# 8x8x8_LEDCUBE_Electronics.net
KiCad netlist of a schematic drawn in EAGLE
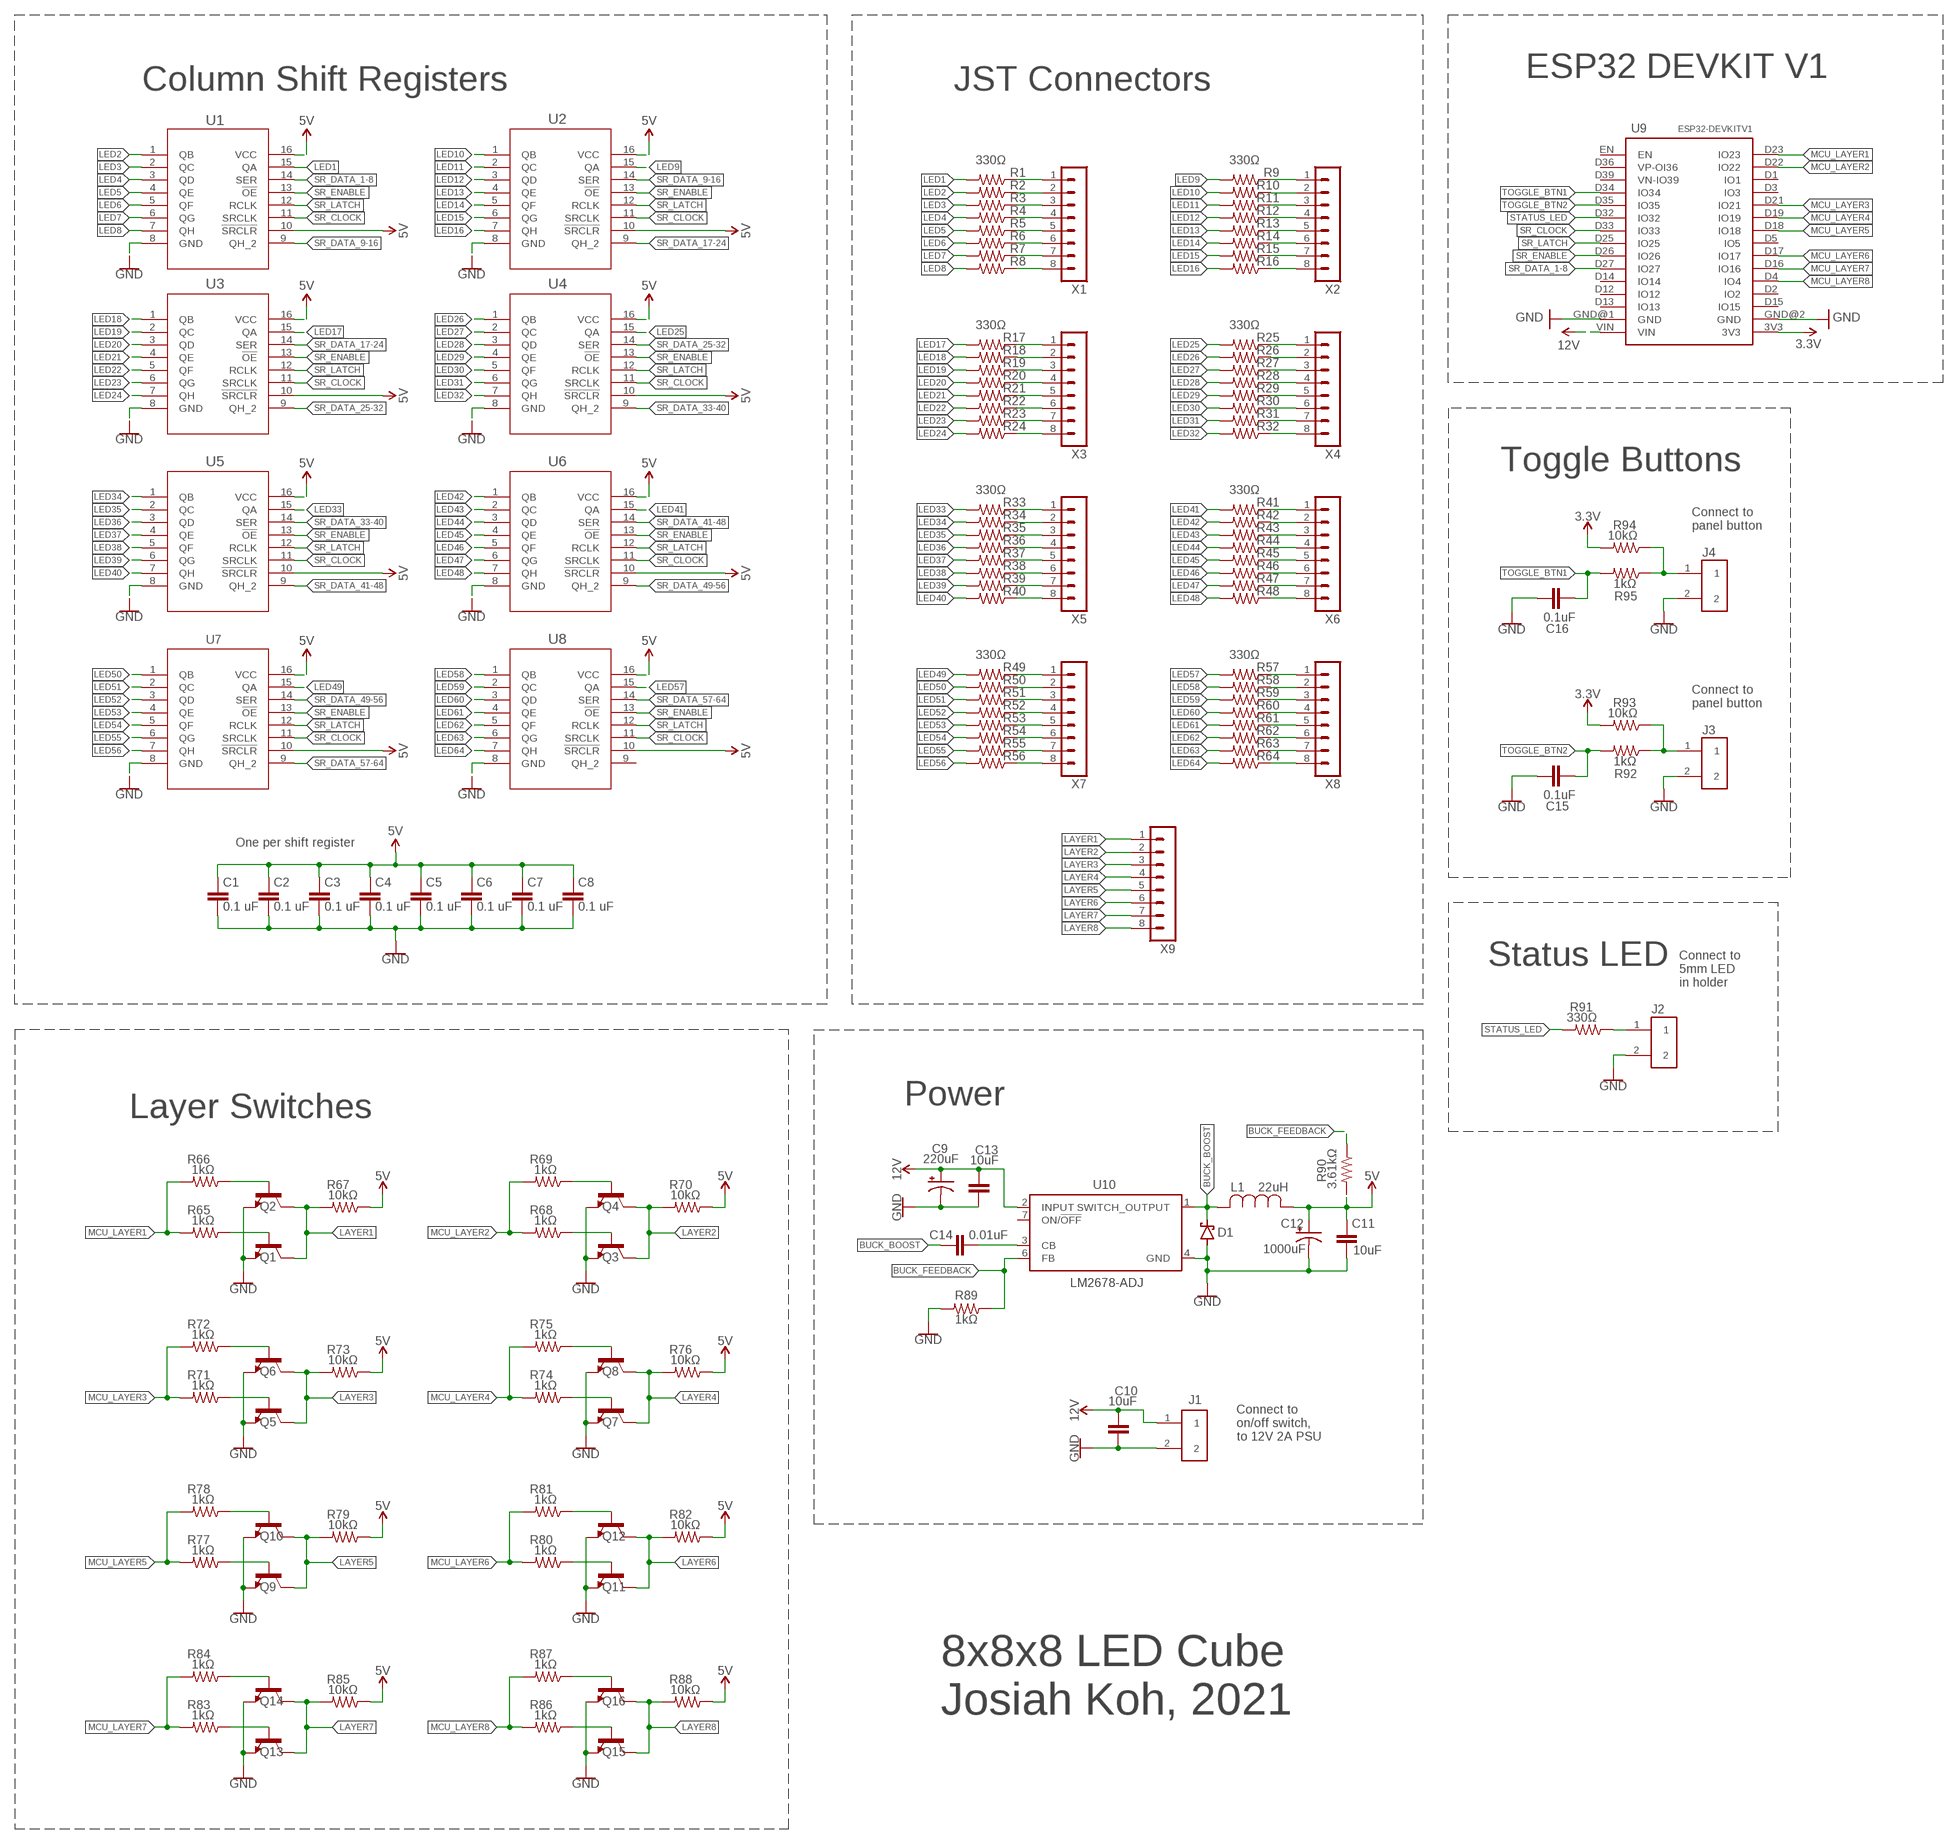
[diagram p0: schematic, sheet 1]

(export (version "E")
  (design (tool "Eeschema 10.0.6"))
  (components
    (comp (ref "C1")
      (value "0.1 uF")
      (footprint "eagle-import:C0805")
      (libsource (lib "eagle-import") (part "C-EUC0805"))
    )
    (comp (ref "C2")
      (value "0.1 uF")
      (footprint "eagle-import:C0805")
      (libsource (lib "eagle-import") (part "C-EUC0805"))
    )
    (comp (ref "C3")
      (value "0.1 uF")
      (footprint "eagle-import:C0805")
      (libsource (lib "eagle-import") (part "C-EUC0805"))
    )
    (comp (ref "C4")
      (value "0.1 uF")
      (footprint "eagle-import:C0805")
      (libsource (lib "eagle-import") (part "C-EUC0805"))
    )
    (comp (ref "C5")
      (value "0.1 uF")
      (footprint "eagle-import:C0805")
      (libsource (lib "eagle-import") (part "C-EUC0805"))
    )
    (comp (ref "C6")
      (value "0.1 uF")
      (footprint "eagle-import:C0805")
      (libsource (lib "eagle-import") (part "C-EUC0805"))
    )
    (comp (ref "C7")
      (value "0.1 uF")
      (footprint "eagle-import:C0805")
      (libsource (lib "eagle-import") (part "C-EUC0805"))
    )
    (comp (ref "C8")
      (value "0.1 uF")
      (footprint "eagle-import:C0805")
      (libsource (lib "eagle-import") (part "C-EUC0805"))
    )
    (comp (ref "C9")
      (value "220uF")
      (footprint "eagle-import:E3,5-10")
      (libsource (lib "eagle-import") (part "CPOL-USE3.5-10"))
    )
    (comp (ref "C10")
      (value "10uF")
      (footprint "eagle-import:C0805")
      (libsource (lib "eagle-import") (part "C-EUC0805"))
    )
    (comp (ref "C11")
      (value "10uF")
      (footprint "eagle-import:C0805")
      (libsource (lib "eagle-import") (part "C-EUC0805"))
    )
    (comp (ref "C12")
      (value "1000uF")
      (footprint "eagle-import:E3,5-10")
      (libsource (lib "eagle-import") (part "CPOL-USE3.5-10"))
    )
    (comp (ref "C13")
      (value "10uF")
      (footprint "eagle-import:C0805")
      (libsource (lib "eagle-import") (part "C-EUC0805"))
    )
    (comp (ref "C14")
      (value "0.01uF")
      (footprint "eagle-import:C0805")
      (libsource (lib "eagle-import") (part "C-EUC0805"))
    )
    (comp (ref "C15")
      (value "0.1uF")
      (footprint "eagle-import:C0805")
      (libsource (lib "eagle-import") (part "C-EUC0805"))
    )
    (comp (ref "C16")
      (value "0.1uF")
      (footprint "eagle-import:C0805")
      (libsource (lib "eagle-import") (part "C-EUC0805"))
    )
    (comp (ref "D1")
      (value "STPS5L60S")
      (footprint "eagle-import:SMC")
      (libsource (lib "eagle-import") (part "SCHOTTKY-DIODESMC"))
    )
    (comp (ref "J1")
      (value "1935161")
      (footprint "eagle-import:PHOENIX_1935161")
      (fields (field (name "DIGI-KEY_PART_NUMBER") "277-1667-ND") (field (name "MF") "Phoenix Contact"))
      (libsource (lib "eagle-import") (part "1935161"))
    )
    (comp (ref "J2")
      (value "1935161")
      (footprint "eagle-import:PHOENIX_1935161")
      (fields (field (name "DIGI-KEY_PART_NUMBER") "277-1667-ND") (field (name "MF") "Phoenix Contact"))
      (libsource (lib "eagle-import") (part "1935161"))
    )
    (comp (ref "J3")
      (value "1935161")
      (footprint "eagle-import:PHOENIX_1935161")
      (fields (field (name "DIGI-KEY_PART_NUMBER") "277-1667-ND") (field (name "MF") "Phoenix Contact"))
      (libsource (lib "eagle-import") (part "1935161"))
    )
    (comp (ref "J4")
      (value "1935161")
      (footprint "eagle-import:PHOENIX_1935161")
      (fields (field (name "DIGI-KEY_PART_NUMBER") "277-1667-ND") (field (name "MF") "Phoenix Contact"))
      (libsource (lib "eagle-import") (part "1935161"))
    )
    (comp (ref "L1")
      (value "22uH")
      (footprint "eagle-import:AIAP-03_ABR")
      (fields (field (name "MANUFACTURER_PART_NUMBER") "AIAP-03-220K"))
      (libsource (lib "eagle-import") (part "AIAP-03-220K"))
    )
    (comp (ref "Q1")
      (value "600mA/40V")
      (footprint "eagle-import:TO-92")
      (libsource (lib "eagle-import") (part "TRANS_NPN-P2N2222A"))
    )
    (comp (ref "Q2")
      (value "600mA/40V")
      (footprint "eagle-import:TO-92")
      (libsource (lib "eagle-import") (part "TRANS_NPN-P2N2222A"))
    )
    (comp (ref "Q3")
      (value "600mA/40V")
      (footprint "eagle-import:TO-92")
      (libsource (lib "eagle-import") (part "TRANS_NPN-P2N2222A"))
    )
    (comp (ref "Q4")
      (value "600mA/40V")
      (footprint "eagle-import:TO-92")
      (libsource (lib "eagle-import") (part "TRANS_NPN-P2N2222A"))
    )
    (comp (ref "Q5")
      (value "600mA/40V")
      (footprint "eagle-import:TO-92")
      (libsource (lib "eagle-import") (part "TRANS_NPN-P2N2222A"))
    )
    (comp (ref "Q6")
      (value "600mA/40V")
      (footprint "eagle-import:TO-92")
      (libsource (lib "eagle-import") (part "TRANS_NPN-P2N2222A"))
    )
    (comp (ref "Q7")
      (value "600mA/40V")
      (footprint "eagle-import:TO-92")
      (libsource (lib "eagle-import") (part "TRANS_NPN-P2N2222A"))
    )
    (comp (ref "Q8")
      (value "600mA/40V")
      (footprint "eagle-import:TO-92")
      (libsource (lib "eagle-import") (part "TRANS_NPN-P2N2222A"))
    )
    (comp (ref "Q9")
      (value "600mA/40V")
      (footprint "eagle-import:TO-92")
      (libsource (lib "eagle-import") (part "TRANS_NPN-P2N2222A"))
    )
    (comp (ref "Q10")
      (value "600mA/40V")
      (footprint "eagle-import:TO-92")
      (libsource (lib "eagle-import") (part "TRANS_NPN-P2N2222A"))
    )
    (comp (ref "Q11")
      (value "600mA/40V")
      (footprint "eagle-import:TO-92")
      (libsource (lib "eagle-import") (part "TRANS_NPN-P2N2222A"))
    )
    (comp (ref "Q12")
      (value "600mA/40V")
      (footprint "eagle-import:TO-92")
      (libsource (lib "eagle-import") (part "TRANS_NPN-P2N2222A"))
    )
    (comp (ref "Q13")
      (value "600mA/40V")
      (footprint "eagle-import:TO-92")
      (libsource (lib "eagle-import") (part "TRANS_NPN-P2N2222A"))
    )
    (comp (ref "Q14")
      (value "600mA/40V")
      (footprint "eagle-import:TO-92")
      (libsource (lib "eagle-import") (part "TRANS_NPN-P2N2222A"))
    )
    (comp (ref "Q15")
      (value "600mA/40V")
      (footprint "eagle-import:TO-92")
      (libsource (lib "eagle-import") (part "TRANS_NPN-P2N2222A"))
    )
    (comp (ref "Q16")
      (value "600mA/40V")
      (footprint "eagle-import:TO-92")
      (libsource (lib "eagle-import") (part "TRANS_NPN-P2N2222A"))
    )
    (comp (ref "R1")
      (value "330Ω")
      (footprint "eagle-import:R0805")
      (libsource (lib "eagle-import") (part "R-US_R0805"))
    )
    (comp (ref "R2")
      (value "330Ω")
      (footprint "eagle-import:R0805")
      (libsource (lib "eagle-import") (part "R-US_R0805"))
    )
    (comp (ref "R3")
      (value "330Ω")
      (footprint "eagle-import:R0805")
      (libsource (lib "eagle-import") (part "R-US_R0805"))
    )
    (comp (ref "R4")
      (value "330Ω")
      (footprint "eagle-import:R0805")
      (libsource (lib "eagle-import") (part "R-US_R0805"))
    )
    (comp (ref "R5")
      (value "330Ω")
      (footprint "eagle-import:R0805")
      (libsource (lib "eagle-import") (part "R-US_R0805"))
    )
    (comp (ref "R6")
      (value "330Ω")
      (footprint "eagle-import:R0805")
      (libsource (lib "eagle-import") (part "R-US_R0805"))
    )
    (comp (ref "R7")
      (value "330Ω")
      (footprint "eagle-import:R0805")
      (libsource (lib "eagle-import") (part "R-US_R0805"))
    )
    (comp (ref "R8")
      (value "330Ω")
      (footprint "eagle-import:R0805")
      (libsource (lib "eagle-import") (part "R-US_R0805"))
    )
    (comp (ref "R9")
      (value "330Ω")
      (footprint "eagle-import:R0805")
      (libsource (lib "eagle-import") (part "R-US_R0805"))
    )
    (comp (ref "R10")
      (value "330Ω")
      (footprint "eagle-import:R0805")
      (libsource (lib "eagle-import") (part "R-US_R0805"))
    )
    (comp (ref "R11")
      (value "330Ω")
      (footprint "eagle-import:R0805")
      (libsource (lib "eagle-import") (part "R-US_R0805"))
    )
    (comp (ref "R12")
      (value "330Ω")
      (footprint "eagle-import:R0805")
      (libsource (lib "eagle-import") (part "R-US_R0805"))
    )
    (comp (ref "R13")
      (value "330Ω")
      (footprint "eagle-import:R0805")
      (libsource (lib "eagle-import") (part "R-US_R0805"))
    )
    (comp (ref "R14")
      (value "330Ω")
      (footprint "eagle-import:R0805")
      (libsource (lib "eagle-import") (part "R-US_R0805"))
    )
    (comp (ref "R15")
      (value "330Ω")
      (footprint "eagle-import:R0805")
      (libsource (lib "eagle-import") (part "R-US_R0805"))
    )
    (comp (ref "R16")
      (value "330Ω")
      (footprint "eagle-import:R0805")
      (libsource (lib "eagle-import") (part "R-US_R0805"))
    )
    (comp (ref "R17")
      (value "330Ω")
      (footprint "eagle-import:R0805")
      (libsource (lib "eagle-import") (part "R-US_R0805"))
    )
    (comp (ref "R18")
      (value "330Ω")
      (footprint "eagle-import:R0805")
      (libsource (lib "eagle-import") (part "R-US_R0805"))
    )
    (comp (ref "R19")
      (value "330Ω")
      (footprint "eagle-import:R0805")
      (libsource (lib "eagle-import") (part "R-US_R0805"))
    )
    (comp (ref "R20")
      (value "330Ω")
      (footprint "eagle-import:R0805")
      (libsource (lib "eagle-import") (part "R-US_R0805"))
    )
    (comp (ref "R21")
      (value "330Ω")
      (footprint "eagle-import:R0805")
      (libsource (lib "eagle-import") (part "R-US_R0805"))
    )
    (comp (ref "R22")
      (value "330Ω")
      (footprint "eagle-import:R0805")
      (libsource (lib "eagle-import") (part "R-US_R0805"))
    )
    (comp (ref "R23")
      (value "330Ω")
      (footprint "eagle-import:R0805")
      (libsource (lib "eagle-import") (part "R-US_R0805"))
    )
    (comp (ref "R24")
      (value "330Ω")
      (footprint "eagle-import:R0805")
      (libsource (lib "eagle-import") (part "R-US_R0805"))
    )
    (comp (ref "R25")
      (value "330Ω")
      (footprint "eagle-import:R0805")
      (libsource (lib "eagle-import") (part "R-US_R0805"))
    )
    (comp (ref "R26")
      (value "330Ω")
      (footprint "eagle-import:R0805")
      (libsource (lib "eagle-import") (part "R-US_R0805"))
    )
    (comp (ref "R27")
      (value "330Ω")
      (footprint "eagle-import:R0805")
      (libsource (lib "eagle-import") (part "R-US_R0805"))
    )
    (comp (ref "R28")
      (value "330Ω")
      (footprint "eagle-import:R0805")
      (libsource (lib "eagle-import") (part "R-US_R0805"))
    )
    (comp (ref "R29")
      (value "330Ω")
      (footprint "eagle-import:R0805")
      (libsource (lib "eagle-import") (part "R-US_R0805"))
    )
    (comp (ref "R30")
      (value "330Ω")
      (footprint "eagle-import:R0805")
      (libsource (lib "eagle-import") (part "R-US_R0805"))
    )
    (comp (ref "R31")
      (value "330Ω")
      (footprint "eagle-import:R0805")
      (libsource (lib "eagle-import") (part "R-US_R0805"))
    )
    (comp (ref "R32")
      (value "330Ω")
      (footprint "eagle-import:R0805")
      (libsource (lib "eagle-import") (part "R-US_R0805"))
    )
    (comp (ref "R33")
      (value "330Ω")
      (footprint "eagle-import:R0805")
      (libsource (lib "eagle-import") (part "R-US_R0805"))
    )
    (comp (ref "R34")
      (value "330Ω")
      (footprint "eagle-import:R0805")
      (libsource (lib "eagle-import") (part "R-US_R0805"))
    )
    (comp (ref "R35")
      (value "330Ω")
      (footprint "eagle-import:R0805")
      (libsource (lib "eagle-import") (part "R-US_R0805"))
    )
    (comp (ref "R36")
      (value "330Ω")
      (footprint "eagle-import:R0805")
      (libsource (lib "eagle-import") (part "R-US_R0805"))
    )
    (comp (ref "R37")
      (value "330Ω")
      (footprint "eagle-import:R0805")
      (libsource (lib "eagle-import") (part "R-US_R0805"))
    )
    (comp (ref "R38")
      (value "330Ω")
      (footprint "eagle-import:R0805")
      (libsource (lib "eagle-import") (part "R-US_R0805"))
    )
    (comp (ref "R39")
      (value "330Ω")
      (footprint "eagle-import:R0805")
      (libsource (lib "eagle-import") (part "R-US_R0805"))
    )
    (comp (ref "R40")
      (value "330Ω")
      (footprint "eagle-import:R0805")
      (libsource (lib "eagle-import") (part "R-US_R0805"))
    )
    (comp (ref "R41")
      (value "330Ω")
      (footprint "eagle-import:R0805")
      (libsource (lib "eagle-import") (part "R-US_R0805"))
    )
    (comp (ref "R42")
      (value "330Ω")
      (footprint "eagle-import:R0805")
      (libsource (lib "eagle-import") (part "R-US_R0805"))
    )
    (comp (ref "R43")
      (value "330Ω")
      (footprint "eagle-import:R0805")
      (libsource (lib "eagle-import") (part "R-US_R0805"))
    )
    (comp (ref "R44")
      (value "330Ω")
      (footprint "eagle-import:R0805")
      (libsource (lib "eagle-import") (part "R-US_R0805"))
    )
    (comp (ref "R45")
      (value "330Ω")
      (footprint "eagle-import:R0805")
      (libsource (lib "eagle-import") (part "R-US_R0805"))
    )
    (comp (ref "R46")
      (value "330Ω")
      (footprint "eagle-import:R0805")
      (libsource (lib "eagle-import") (part "R-US_R0805"))
    )
    (comp (ref "R47")
      (value "330Ω")
      (footprint "eagle-import:R0805")
      (libsource (lib "eagle-import") (part "R-US_R0805"))
    )
    (comp (ref "R48")
      (value "330Ω")
      (footprint "eagle-import:R0805")
      (libsource (lib "eagle-import") (part "R-US_R0805"))
    )
    (comp (ref "R49")
      (value "330Ω")
      (footprint "eagle-import:R0805")
      (libsource (lib "eagle-import") (part "R-US_R0805"))
    )
    (comp (ref "R50")
      (value "330Ω")
      (footprint "eagle-import:R0805")
      (libsource (lib "eagle-import") (part "R-US_R0805"))
    )
    (comp (ref "R51")
      (value "330Ω")
      (footprint "eagle-import:R0805")
      (libsource (lib "eagle-import") (part "R-US_R0805"))
    )
    (comp (ref "R52")
      (value "330Ω")
      (footprint "eagle-import:R0805")
      (libsource (lib "eagle-import") (part "R-US_R0805"))
    )
    (comp (ref "R53")
      (value "330Ω")
      (footprint "eagle-import:R0805")
      (libsource (lib "eagle-import") (part "R-US_R0805"))
    )
    (comp (ref "R54")
      (value "330Ω")
      (footprint "eagle-import:R0805")
      (libsource (lib "eagle-import") (part "R-US_R0805"))
    )
    (comp (ref "R55")
      (value "330Ω")
      (footprint "eagle-import:R0805")
      (libsource (lib "eagle-import") (part "R-US_R0805"))
    )
    (comp (ref "R56")
      (value "330Ω")
      (footprint "eagle-import:R0805")
      (libsource (lib "eagle-import") (part "R-US_R0805"))
    )
    (comp (ref "R57")
      (value "330Ω")
      (footprint "eagle-import:R0805")
      (libsource (lib "eagle-import") (part "R-US_R0805"))
    )
    (comp (ref "R58")
      (value "330Ω")
      (footprint "eagle-import:R0805")
      (libsource (lib "eagle-import") (part "R-US_R0805"))
    )
    (comp (ref "R59")
      (value "330Ω")
      (footprint "eagle-import:R0805")
      (libsource (lib "eagle-import") (part "R-US_R0805"))
    )
    (comp (ref "R60")
      (value "330Ω")
      (footprint "eagle-import:R0805")
      (libsource (lib "eagle-import") (part "R-US_R0805"))
    )
    (comp (ref "R61")
      (value "330Ω")
      (footprint "eagle-import:R0805")
      (libsource (lib "eagle-import") (part "R-US_R0805"))
    )
    (comp (ref "R62")
      (value "330Ω")
      (footprint "eagle-import:R0805")
      (libsource (lib "eagle-import") (part "R-US_R0805"))
    )
    (comp (ref "R63")
      (value "330Ω")
      (footprint "eagle-import:R0805")
      (libsource (lib "eagle-import") (part "R-US_R0805"))
    )
    (comp (ref "R64")
      (value "330Ω")
      (footprint "eagle-import:R0805")
      (libsource (lib "eagle-import") (part "R-US_R0805"))
    )
    (comp (ref "R65")
      (value "1kΩ")
      (footprint "eagle-import:R0805")
      (libsource (lib "eagle-import") (part "R-US_R0805"))
    )
    (comp (ref "R66")
      (value "1kΩ")
      (footprint "eagle-import:R0805")
      (libsource (lib "eagle-import") (part "R-US_R0805"))
    )
    (comp (ref "R67")
      (value "10kΩ")
      (footprint "eagle-import:R0805")
      (libsource (lib "eagle-import") (part "R-US_R0805"))
    )
    (comp (ref "R68")
      (value "1kΩ")
      (footprint "eagle-import:R0805")
      (libsource (lib "eagle-import") (part "R-US_R0805"))
    )
    (comp (ref "R69")
      (value "1kΩ")
      (footprint "eagle-import:R0805")
      (libsource (lib "eagle-import") (part "R-US_R0805"))
    )
    (comp (ref "R70")
      (value "10kΩ")
      (footprint "eagle-import:R0805")
      (libsource (lib "eagle-import") (part "R-US_R0805"))
    )
    (comp (ref "R71")
      (value "1kΩ")
      (footprint "eagle-import:R0805")
      (libsource (lib "eagle-import") (part "R-US_R0805"))
    )
    (comp (ref "R72")
      (value "1kΩ")
      (footprint "eagle-import:R0805")
      (libsource (lib "eagle-import") (part "R-US_R0805"))
    )
    (comp (ref "R73")
      (value "10kΩ")
      (footprint "eagle-import:R0805")
      (libsource (lib "eagle-import") (part "R-US_R0805"))
    )
    (comp (ref "R74")
      (value "1kΩ")
      (footprint "eagle-import:R0805")
      (libsource (lib "eagle-import") (part "R-US_R0805"))
    )
    (comp (ref "R75")
      (value "1kΩ")
      (footprint "eagle-import:R0805")
      (libsource (lib "eagle-import") (part "R-US_R0805"))
    )
    (comp (ref "R76")
      (value "10kΩ")
      (footprint "eagle-import:R0805")
      (libsource (lib "eagle-import") (part "R-US_R0805"))
    )
    (comp (ref "R77")
      (value "1kΩ")
      (footprint "eagle-import:R0805")
      (libsource (lib "eagle-import") (part "R-US_R0805"))
    )
    (comp (ref "R78")
      (value "1kΩ")
      (footprint "eagle-import:R0805")
      (libsource (lib "eagle-import") (part "R-US_R0805"))
    )
    (comp (ref "R79")
      (value "10kΩ")
      (footprint "eagle-import:R0805")
      (libsource (lib "eagle-import") (part "R-US_R0805"))
    )
    (comp (ref "R80")
      (value "1kΩ")
      (footprint "eagle-import:R0805")
      (libsource (lib "eagle-import") (part "R-US_R0805"))
    )
    (comp (ref "R81")
      (value "1kΩ")
      (footprint "eagle-import:R0805")
      (libsource (lib "eagle-import") (part "R-US_R0805"))
    )
    (comp (ref "R82")
      (value "10kΩ")
      (footprint "eagle-import:R0805")
      (libsource (lib "eagle-import") (part "R-US_R0805"))
    )
    (comp (ref "R83")
      (value "1kΩ")
      (footprint "eagle-import:R0805")
      (libsource (lib "eagle-import") (part "R-US_R0805"))
    )
    (comp (ref "R84")
      (value "1kΩ")
      (footprint "eagle-import:R0805")
      (libsource (lib "eagle-import") (part "R-US_R0805"))
    )
    (comp (ref "R85")
      (value "10kΩ")
      (footprint "eagle-import:R0805")
      (libsource (lib "eagle-import") (part "R-US_R0805"))
    )
    (comp (ref "R86")
      (value "1kΩ")
      (footprint "eagle-import:R0805")
      (libsource (lib "eagle-import") (part "R-US_R0805"))
    )
    (comp (ref "R87")
      (value "1kΩ")
      (footprint "eagle-import:R0805")
      (libsource (lib "eagle-import") (part "R-US_R0805"))
    )
    (comp (ref "R88")
      (value "10kΩ")
      (footprint "eagle-import:R0805")
      (libsource (lib "eagle-import") (part "R-US_R0805"))
    )
    (comp (ref "R89")
      (value "1kΩ")
      (footprint "eagle-import:R0805")
      (libsource (lib "eagle-import") (part "R-US_R0805"))
    )
    (comp (ref "R90")
      (value "3.61kΩ")
      (footprint "eagle-import:R0805")
      (libsource (lib "eagle-import") (part "R-US_R0805"))
    )
    (comp (ref "R91")
      (value "330Ω")
      (footprint "eagle-import:R0805")
      (libsource (lib "eagle-import") (part "R-US_R0805"))
    )
    (comp (ref "R92")
      (value "1kΩ")
      (footprint "eagle-import:R0805")
      (libsource (lib "eagle-import") (part "R-US_R0805"))
    )
    (comp (ref "R93")
      (value "10kΩ")
      (footprint "eagle-import:R0805")
      (libsource (lib "eagle-import") (part "R-US_R0805"))
    )
    (comp (ref "R94")
      (value "10kΩ")
      (footprint "eagle-import:R0805")
      (libsource (lib "eagle-import") (part "R-US_R0805"))
    )
    (comp (ref "R95")
      (value "1kΩ")
      (footprint "eagle-import:R0805")
      (libsource (lib "eagle-import") (part "R-US_R0805"))
    )
    (comp (ref "U1")
      (value "SN74HC595N")
      (footprint "eagle-import:N16")
      (fields
        (field (name "GENERIC_PART_NUMBER") "SN74HC595")
        (field (name "MANUFACTURER") "Texas Instruments")
      )
      (libsource (lib "eagle-import") (part "SN74HC595N"))
    )
    (comp (ref "U2")
      (value "SN74HC595N")
      (footprint "eagle-import:N16")
      (fields
        (field (name "GENERIC_PART_NUMBER") "SN74HC595")
        (field (name "MANUFACTURER") "Texas Instruments")
      )
      (libsource (lib "eagle-import") (part "SN74HC595N"))
    )
    (comp (ref "U3")
      (value "SN74HC595N")
      (footprint "eagle-import:N16")
      (fields
        (field (name "GENERIC_PART_NUMBER") "SN74HC595")
        (field (name "MANUFACTURER") "Texas Instruments")
      )
      (libsource (lib "eagle-import") (part "SN74HC595N"))
    )
    (comp (ref "U4")
      (value "SN74HC595N")
      (footprint "eagle-import:N16")
      (fields
        (field (name "GENERIC_PART_NUMBER") "SN74HC595")
        (field (name "MANUFACTURER") "Texas Instruments")
      )
      (libsource (lib "eagle-import") (part "SN74HC595N"))
    )
    (comp (ref "U5")
      (value "SN74HC595N")
      (footprint "eagle-import:N16")
      (fields
        (field (name "GENERIC_PART_NUMBER") "SN74HC595")
        (field (name "MANUFACTURER") "Texas Instruments")
      )
      (libsource (lib "eagle-import") (part "SN74HC595N"))
    )
    (comp (ref "U6")
      (value "SN74HC595N")
      (footprint "eagle-import:N16")
      (fields
        (field (name "GENERIC_PART_NUMBER") "SN74HC595")
        (field (name "MANUFACTURER") "Texas Instruments")
      )
      (libsource (lib "eagle-import") (part "SN74HC595N"))
    )
    (comp (ref "U7")
      (value "SN74HC595N")
      (footprint "eagle-import:N16")
      (fields
        (field (name "GENERIC_PART_NUMBER") "SN74HC595")
        (field (name "MANUFACTURER") "Texas Instruments")
      )
      (libsource (lib "eagle-import") (part "SN74HC595N"))
    )
    (comp (ref "U8")
      (value "SN74HC595N")
      (footprint "eagle-import:N16")
      (fields
        (field (name "GENERIC_PART_NUMBER") "SN74HC595")
        (field (name "MANUFACTURER") "Texas Instruments")
      )
      (libsource (lib "eagle-import") (part "SN74HC595N"))
    )
    (comp (ref "U9")
      (value "ESP32DEVKITV1")
      (footprint "eagle-import:ESP32-DEVKITV1")
      (libsource (lib "eagle-import") (part "ESP32DEVKITV1"))
    )
    (comp (ref "U10")
      (value "LM2678-ADJ")
      (footprint "eagle-import:TO127P1041X469X2199-7N")
      (fields
        (field (name "DIGI-KEY_PART_NUMBER") "LM2678T-ADJ/NOPB-ND")
        (field (name "MF") "Texas Instruments")
        (field (name "MP") "LM2678T-ADJ/NOPB")
        (field (name "SPICEPREFIX") "X")
      )
      (libsource (lib "eagle-import") (part "LM2678T-ADJ/NOPB"))
    )
    (comp (ref "X1")
      (value "B8B-PH-KL")
      (footprint "eagle-import:B8B-PH-K-S")
      (libsource (lib "eagle-import") (part "B8B-PH-KL"))
    )
    (comp (ref "X2")
      (value "B8B-PH-KL")
      (footprint "eagle-import:B8B-PH-K-S")
      (libsource (lib "eagle-import") (part "B8B-PH-KL"))
    )
    (comp (ref "X3")
      (value "B8B-PH-KL")
      (footprint "eagle-import:B8B-PH-K-S")
      (libsource (lib "eagle-import") (part "B8B-PH-KL"))
    )
    (comp (ref "X4")
      (value "B8B-PH-KL")
      (footprint "eagle-import:B8B-PH-K-S")
      (libsource (lib "eagle-import") (part "B8B-PH-KL"))
    )
    (comp (ref "X5")
      (value "B8B-PH-KL")
      (footprint "eagle-import:B8B-PH-K-S")
      (libsource (lib "eagle-import") (part "B8B-PH-KL"))
    )
    (comp (ref "X6")
      (value "B8B-PH-KL")
      (footprint "eagle-import:B8B-PH-K-S")
      (libsource (lib "eagle-import") (part "B8B-PH-KL"))
    )
    (comp (ref "X7")
      (value "B8B-PH-KL")
      (footprint "eagle-import:B8B-PH-K-S")
      (libsource (lib "eagle-import") (part "B8B-PH-KL"))
    )
    (comp (ref "X8")
      (value "B8B-PH-KL")
      (footprint "eagle-import:B8B-PH-K-S")
      (libsource (lib "eagle-import") (part "B8B-PH-KL"))
    )
    (comp (ref "X9")
      (value "B8B-PH-KL")
      (footprint "eagle-import:B8B-PH-K-S")
      (libsource (lib "eagle-import") (part "B8B-PH-KL"))
    )
  )
  (nets
    (net (code "1") (name "3.3V") (class "Default")
      (node (ref "R93") (pin "2") (pinfunction "2_2") (pintype "passive"))
      (node (ref "R94") (pin "2") (pinfunction "2_2") (pintype "passive"))
      (node (ref "U9") (pin "3V3") (pinfunction "3V3_3V3") (pintype "bidirectional"))
    )
    (net (code "2") (name "5V") (class "Default")
      (node (ref "C1") (pin "1") (pinfunction "1_1") (pintype "passive"))
      (node (ref "C11") (pin "1") (pinfunction "1_1") (pintype "passive"))
      (node (ref "C12") (pin "+") (pinfunction "+_+") (pintype "passive"))
      (node (ref "C2") (pin "1") (pinfunction "1_1") (pintype "passive"))
      (node (ref "C3") (pin "1") (pinfunction "1_1") (pintype "passive"))
      (node (ref "C4") (pin "1") (pinfunction "1_1") (pintype "passive"))
      (node (ref "C5") (pin "1") (pinfunction "1_1") (pintype "passive"))
      (node (ref "C6") (pin "1") (pinfunction "1_1") (pintype "passive"))
      (node (ref "C7") (pin "1") (pinfunction "1_1") (pintype "passive"))
      (node (ref "C8") (pin "1") (pinfunction "1_1") (pintype "passive"))
      (node (ref "L1") (pin "1") (pinfunction "1_1") (pintype "passive"))
      (node (ref "R67") (pin "1") (pinfunction "1_1") (pintype "passive"))
      (node (ref "R70") (pin "1") (pinfunction "1_1") (pintype "passive"))
      (node (ref "R73") (pin "1") (pinfunction "1_1") (pintype "passive"))
      (node (ref "R76") (pin "1") (pinfunction "1_1") (pintype "passive"))
      (node (ref "R79") (pin "1") (pinfunction "1_1") (pintype "passive"))
      (node (ref "R82") (pin "1") (pinfunction "1_1") (pintype "passive"))
      (node (ref "R85") (pin "1") (pinfunction "1_1") (pintype "passive"))
      (node (ref "R88") (pin "1") (pinfunction "1_1") (pintype "passive"))
      (node (ref "R90") (pin "2") (pinfunction "2_2") (pintype "passive"))
      (node (ref "U1") (pin "10") (pinfunction "~{SRCLR}_10") (pintype "input"))
      (node (ref "U1") (pin "16") (pinfunction "VCC_16") (pintype "power_in"))
      (node (ref "U2") (pin "10") (pinfunction "~{SRCLR}_10") (pintype "input"))
      (node (ref "U2") (pin "16") (pinfunction "VCC_16") (pintype "power_in"))
      (node (ref "U3") (pin "10") (pinfunction "~{SRCLR}_10") (pintype "input"))
      (node (ref "U3") (pin "16") (pinfunction "VCC_16") (pintype "power_in"))
      (node (ref "U4") (pin "10") (pinfunction "~{SRCLR}_10") (pintype "input"))
      (node (ref "U4") (pin "16") (pinfunction "VCC_16") (pintype "power_in"))
      (node (ref "U5") (pin "10") (pinfunction "~{SRCLR}_10") (pintype "input"))
      (node (ref "U5") (pin "16") (pinfunction "VCC_16") (pintype "power_in"))
      (node (ref "U6") (pin "10") (pinfunction "~{SRCLR}_10") (pintype "input"))
      (node (ref "U6") (pin "16") (pinfunction "VCC_16") (pintype "power_in"))
      (node (ref "U7") (pin "10") (pinfunction "~{SRCLR}_10") (pintype "input"))
      (node (ref "U7") (pin "16") (pinfunction "VCC_16") (pintype "power_in"))
      (node (ref "U8") (pin "10") (pinfunction "~{SRCLR}_10") (pintype "input"))
      (node (ref "U8") (pin "16") (pinfunction "VCC_16") (pintype "power_in"))
    )
    (net (code "3") (name "12V") (class "Default")
      (node (ref "C10") (pin "1") (pinfunction "1_1") (pintype "passive"))
      (node (ref "C13") (pin "1") (pinfunction "1_1") (pintype "passive"))
      (node (ref "C9") (pin "+") (pinfunction "+_+") (pintype "passive"))
      (node (ref "J1") (pin "1") (pinfunction "1_1") (pintype "passive"))
      (node (ref "U10") (pin "2") (pinfunction "INPUT_2") (pintype "input"))
      (node (ref "U9") (pin "VIN") (pinfunction "VIN_VIN") (pintype "bidirectional"))
    )
    (net (code "4") (name "BUCK_BOOST") (class "Default")
      (node (ref "C14") (pin "1") (pinfunction "1_1") (pintype "passive"))
      (node (ref "D1") (pin "C") (pinfunction "C_C") (pintype "passive"))
      (node (ref "L1") (pin "2") (pinfunction "2_2") (pintype "passive"))
      (node (ref "U10") (pin "1") (pinfunction "SWITCH_OUTPUT_1") (pintype "output"))
    )
    (net (code "5") (name "BUCK_FEEDBACK") (class "Default")
      (node (ref "R89") (pin "1") (pinfunction "1_1") (pintype "passive"))
      (node (ref "R90") (pin "1") (pinfunction "1_1") (pintype "passive"))
      (node (ref "U10") (pin "6") (pinfunction "FB_6") (pintype "input"))
    )
    (net (code "6") (name "GND") (class "Default")
      (node (ref "C1") (pin "2") (pinfunction "2_2") (pintype "passive"))
      (node (ref "C10") (pin "2") (pinfunction "2_2") (pintype "passive"))
      (node (ref "C11") (pin "2") (pinfunction "2_2") (pintype "passive"))
      (node (ref "C12") (pin "-") (pinfunction "-_-") (pintype "passive"))
      (node (ref "C13") (pin "2") (pinfunction "2_2") (pintype "passive"))
      (node (ref "C15") (pin "2") (pinfunction "2_2") (pintype "passive"))
      (node (ref "C16") (pin "2") (pinfunction "2_2") (pintype "passive"))
      (node (ref "C2") (pin "2") (pinfunction "2_2") (pintype "passive"))
      (node (ref "C3") (pin "2") (pinfunction "2_2") (pintype "passive"))
      (node (ref "C4") (pin "2") (pinfunction "2_2") (pintype "passive"))
      (node (ref "C5") (pin "2") (pinfunction "2_2") (pintype "passive"))
      (node (ref "C6") (pin "2") (pinfunction "2_2") (pintype "passive"))
      (node (ref "C7") (pin "2") (pinfunction "2_2") (pintype "passive"))
      (node (ref "C8") (pin "2") (pinfunction "2_2") (pintype "passive"))
      (node (ref "C9") (pin "-") (pinfunction "-_-") (pintype "passive"))
      (node (ref "D1") (pin "A") (pinfunction "A_A") (pintype "passive"))
      (node (ref "J1") (pin "2") (pinfunction "2_2") (pintype "passive"))
      (node (ref "J2") (pin "2") (pinfunction "2_2") (pintype "passive"))
      (node (ref "J3") (pin "2") (pinfunction "2_2") (pintype "passive"))
      (node (ref "J4") (pin "2") (pinfunction "2_2") (pintype "passive"))
      (node (ref "Q1") (pin "3") (pinfunction "E_3") (pintype "passive"))
      (node (ref "Q10") (pin "3") (pinfunction "E_3") (pintype "passive"))
      (node (ref "Q11") (pin "3") (pinfunction "E_3") (pintype "passive"))
      (node (ref "Q12") (pin "3") (pinfunction "E_3") (pintype "passive"))
      (node (ref "Q13") (pin "3") (pinfunction "E_3") (pintype "passive"))
      (node (ref "Q14") (pin "3") (pinfunction "E_3") (pintype "passive"))
      (node (ref "Q15") (pin "3") (pinfunction "E_3") (pintype "passive"))
      (node (ref "Q16") (pin "3") (pinfunction "E_3") (pintype "passive"))
      (node (ref "Q2") (pin "3") (pinfunction "E_3") (pintype "passive"))
      (node (ref "Q3") (pin "3") (pinfunction "E_3") (pintype "passive"))
      (node (ref "Q4") (pin "3") (pinfunction "E_3") (pintype "passive"))
      (node (ref "Q5") (pin "3") (pinfunction "E_3") (pintype "passive"))
      (node (ref "Q6") (pin "3") (pinfunction "E_3") (pintype "passive"))
      (node (ref "Q7") (pin "3") (pinfunction "E_3") (pintype "passive"))
      (node (ref "Q8") (pin "3") (pinfunction "E_3") (pintype "passive"))
      (node (ref "Q9") (pin "3") (pinfunction "E_3") (pintype "passive"))
      (node (ref "R89") (pin "2") (pinfunction "2_2") (pintype "passive"))
      (node (ref "U1") (pin "8") (pinfunction "GND_8") (pintype "power_in"))
      (node (ref "U10") (pin "4") (pinfunction "GND_4") (pintype "power_in"))
      (node (ref "U2") (pin "8") (pinfunction "GND_8") (pintype "power_in"))
      (node (ref "U3") (pin "8") (pinfunction "GND_8") (pintype "power_in"))
      (node (ref "U4") (pin "8") (pinfunction "GND_8") (pintype "power_in"))
      (node (ref "U5") (pin "8") (pinfunction "GND_8") (pintype "power_in"))
      (node (ref "U6") (pin "8") (pinfunction "GND_8") (pintype "power_in"))
      (node (ref "U7") (pin "8") (pinfunction "GND_8") (pintype "power_in"))
      (node (ref "U8") (pin "8") (pinfunction "GND_8") (pintype "power_in"))
      (node (ref "U9") (pin "GND@1") (pinfunction "GND_GND@1") (pintype "bidirectional"))
      (node (ref "U9") (pin "GND@2") (pinfunction "GND_GND@2") (pintype "bidirectional"))
    )
    (net (code "7") (name "LAYER1") (class "Default")
      (node (ref "Q1") (pin "1") (pinfunction "C_1") (pintype "passive"))
      (node (ref "Q2") (pin "1") (pinfunction "C_1") (pintype "passive"))
      (node (ref "R67") (pin "2") (pinfunction "2_2") (pintype "passive"))
      (node (ref "X9") (pin "1") (pinfunction "1_1") (pintype "passive"))
    )
    (net (code "8") (name "LAYER2") (class "Default")
      (node (ref "Q3") (pin "1") (pinfunction "C_1") (pintype "passive"))
      (node (ref "Q4") (pin "1") (pinfunction "C_1") (pintype "passive"))
      (node (ref "R70") (pin "2") (pinfunction "2_2") (pintype "passive"))
      (node (ref "X9") (pin "2") (pinfunction "2_2") (pintype "passive"))
    )
    (net (code "9") (name "LAYER3") (class "Default")
      (node (ref "Q5") (pin "1") (pinfunction "C_1") (pintype "passive"))
      (node (ref "Q6") (pin "1") (pinfunction "C_1") (pintype "passive"))
      (node (ref "R73") (pin "2") (pinfunction "2_2") (pintype "passive"))
      (node (ref "X9") (pin "3") (pinfunction "3_3") (pintype "passive"))
    )
    (net (code "10") (name "LAYER4") (class "Default")
      (node (ref "Q7") (pin "1") (pinfunction "C_1") (pintype "passive"))
      (node (ref "Q8") (pin "1") (pinfunction "C_1") (pintype "passive"))
      (node (ref "R76") (pin "2") (pinfunction "2_2") (pintype "passive"))
      (node (ref "X9") (pin "4") (pinfunction "4_4") (pintype "passive"))
    )
    (net (code "11") (name "LAYER5") (class "Default")
      (node (ref "Q10") (pin "1") (pinfunction "C_1") (pintype "passive"))
      (node (ref "Q9") (pin "1") (pinfunction "C_1") (pintype "passive"))
      (node (ref "R79") (pin "2") (pinfunction "2_2") (pintype "passive"))
      (node (ref "X9") (pin "5") (pinfunction "5_5") (pintype "passive"))
    )
    (net (code "12") (name "LAYER6") (class "Default")
      (node (ref "Q11") (pin "1") (pinfunction "C_1") (pintype "passive"))
      (node (ref "Q12") (pin "1") (pinfunction "C_1") (pintype "passive"))
      (node (ref "R82") (pin "2") (pinfunction "2_2") (pintype "passive"))
      (node (ref "X9") (pin "6") (pinfunction "6_6") (pintype "passive"))
    )
    (net (code "13") (name "LAYER7") (class "Default")
      (node (ref "Q13") (pin "1") (pinfunction "C_1") (pintype "passive"))
      (node (ref "Q14") (pin "1") (pinfunction "C_1") (pintype "passive"))
      (node (ref "R85") (pin "2") (pinfunction "2_2") (pintype "passive"))
      (node (ref "X9") (pin "7") (pinfunction "7_7") (pintype "passive"))
    )
    (net (code "14") (name "LAYER8") (class "Default")
      (node (ref "Q15") (pin "1") (pinfunction "C_1") (pintype "passive"))
      (node (ref "Q16") (pin "1") (pinfunction "C_1") (pintype "passive"))
      (node (ref "R88") (pin "2") (pinfunction "2_2") (pintype "passive"))
      (node (ref "X9") (pin "8") (pinfunction "8_8") (pintype "passive"))
    )
    (net (code "15") (name "LED1") (class "Default")
      (node (ref "R1") (pin "2") (pinfunction "2_2") (pintype "passive"))
      (node (ref "U1") (pin "15") (pinfunction "QA_15") (pintype "output"))
    )
    (net (code "16") (name "LED2") (class "Default")
      (node (ref "R2") (pin "2") (pinfunction "2_2") (pintype "passive"))
      (node (ref "U1") (pin "1") (pinfunction "QB_1") (pintype "output"))
    )
    (net (code "17") (name "LED3") (class "Default")
      (node (ref "R3") (pin "2") (pinfunction "2_2") (pintype "passive"))
      (node (ref "U1") (pin "2") (pinfunction "QC_2") (pintype "output"))
    )
    (net (code "18") (name "LED4") (class "Default")
      (node (ref "R4") (pin "2") (pinfunction "2_2") (pintype "passive"))
      (node (ref "U1") (pin "3") (pinfunction "QD_3") (pintype "output"))
    )
    (net (code "19") (name "LED5") (class "Default")
      (node (ref "R5") (pin "2") (pinfunction "2_2") (pintype "passive"))
      (node (ref "U1") (pin "4") (pinfunction "QE_4") (pintype "output"))
    )
    (net (code "20") (name "LED6") (class "Default")
      (node (ref "R6") (pin "2") (pinfunction "2_2") (pintype "passive"))
      (node (ref "U1") (pin "5") (pinfunction "QF_5") (pintype "output"))
    )
    (net (code "21") (name "LED7") (class "Default")
      (node (ref "R7") (pin "2") (pinfunction "2_2") (pintype "passive"))
      (node (ref "U1") (pin "6") (pinfunction "QG_6") (pintype "output"))
    )
    (net (code "22") (name "LED8") (class "Default")
      (node (ref "R8") (pin "2") (pinfunction "2_2") (pintype "passive"))
      (node (ref "U1") (pin "7") (pinfunction "QH_7") (pintype "output"))
    )
    (net (code "23") (name "LED9") (class "Default")
      (node (ref "R9") (pin "2") (pinfunction "2_2") (pintype "passive"))
      (node (ref "U2") (pin "15") (pinfunction "QA_15") (pintype "output"))
    )
    (net (code "24") (name "LED10") (class "Default")
      (node (ref "R10") (pin "2") (pinfunction "2_2") (pintype "passive"))
      (node (ref "U2") (pin "1") (pinfunction "QB_1") (pintype "output"))
    )
    (net (code "25") (name "LED11") (class "Default")
      (node (ref "R11") (pin "2") (pinfunction "2_2") (pintype "passive"))
      (node (ref "U2") (pin "2") (pinfunction "QC_2") (pintype "output"))
    )
    (net (code "26") (name "LED12") (class "Default")
      (node (ref "R12") (pin "2") (pinfunction "2_2") (pintype "passive"))
      (node (ref "U2") (pin "3") (pinfunction "QD_3") (pintype "output"))
    )
    (net (code "27") (name "LED13") (class "Default")
      (node (ref "R13") (pin "2") (pinfunction "2_2") (pintype "passive"))
      (node (ref "U2") (pin "4") (pinfunction "QE_4") (pintype "output"))
    )
    (net (code "28") (name "LED14") (class "Default")
      (node (ref "R14") (pin "2") (pinfunction "2_2") (pintype "passive"))
      (node (ref "U2") (pin "5") (pinfunction "QF_5") (pintype "output"))
    )
    (net (code "29") (name "LED15") (class "Default")
      (node (ref "R15") (pin "2") (pinfunction "2_2") (pintype "passive"))
      (node (ref "U2") (pin "6") (pinfunction "QG_6") (pintype "output"))
    )
    (net (code "30") (name "LED16") (class "Default")
      (node (ref "R16") (pin "2") (pinfunction "2_2") (pintype "passive"))
      (node (ref "U2") (pin "7") (pinfunction "QH_7") (pintype "output"))
    )
    (net (code "31") (name "LED17") (class "Default")
      (node (ref "R17") (pin "2") (pinfunction "2_2") (pintype "passive"))
      (node (ref "U3") (pin "15") (pinfunction "QA_15") (pintype "output"))
    )
    (net (code "32") (name "LED18") (class "Default")
      (node (ref "R18") (pin "2") (pinfunction "2_2") (pintype "passive"))
      (node (ref "U3") (pin "1") (pinfunction "QB_1") (pintype "output"))
    )
    (net (code "33") (name "LED19") (class "Default")
      (node (ref "R19") (pin "2") (pinfunction "2_2") (pintype "passive"))
      (node (ref "U3") (pin "2") (pinfunction "QC_2") (pintype "output"))
    )
    (net (code "34") (name "LED20") (class "Default")
      (node (ref "R20") (pin "2") (pinfunction "2_2") (pintype "passive"))
      (node (ref "U3") (pin "3") (pinfunction "QD_3") (pintype "output"))
    )
    (net (code "35") (name "LED21") (class "Default")
      (node (ref "R21") (pin "2") (pinfunction "2_2") (pintype "passive"))
      (node (ref "U3") (pin "4") (pinfunction "QE_4") (pintype "output"))
    )
    (net (code "36") (name "LED22") (class "Default")
      (node (ref "R22") (pin "2") (pinfunction "2_2") (pintype "passive"))
      (node (ref "U3") (pin "5") (pinfunction "QF_5") (pintype "output"))
    )
    (net (code "37") (name "LED23") (class "Default")
      (node (ref "R23") (pin "2") (pinfunction "2_2") (pintype "passive"))
      (node (ref "U3") (pin "6") (pinfunction "QG_6") (pintype "output"))
    )
    (net (code "38") (name "LED24") (class "Default")
      (node (ref "R24") (pin "2") (pinfunction "2_2") (pintype "passive"))
      (node (ref "U3") (pin "7") (pinfunction "QH_7") (pintype "output"))
    )
    (net (code "39") (name "LED25") (class "Default")
      (node (ref "R25") (pin "2") (pinfunction "2_2") (pintype "passive"))
      (node (ref "U4") (pin "15") (pinfunction "QA_15") (pintype "output"))
    )
    (net (code "40") (name "LED26") (class "Default")
      (node (ref "R26") (pin "2") (pinfunction "2_2") (pintype "passive"))
      (node (ref "U4") (pin "1") (pinfunction "QB_1") (pintype "output"))
    )
    (net (code "41") (name "LED27") (class "Default")
      (node (ref "R27") (pin "2") (pinfunction "2_2") (pintype "passive"))
      (node (ref "U4") (pin "2") (pinfunction "QC_2") (pintype "output"))
    )
    (net (code "42") (name "LED28") (class "Default")
      (node (ref "R28") (pin "2") (pinfunction "2_2") (pintype "passive"))
      (node (ref "U4") (pin "3") (pinfunction "QD_3") (pintype "output"))
    )
    (net (code "43") (name "LED29") (class "Default")
      (node (ref "R29") (pin "2") (pinfunction "2_2") (pintype "passive"))
      (node (ref "U4") (pin "4") (pinfunction "QE_4") (pintype "output"))
    )
    (net (code "44") (name "LED30") (class "Default")
      (node (ref "R30") (pin "2") (pinfunction "2_2") (pintype "passive"))
      (node (ref "U4") (pin "5") (pinfunction "QF_5") (pintype "output"))
    )
    (net (code "45") (name "LED31") (class "Default")
      (node (ref "R31") (pin "2") (pinfunction "2_2") (pintype "passive"))
      (node (ref "U4") (pin "6") (pinfunction "QG_6") (pintype "output"))
    )
    (net (code "46") (name "LED32") (class "Default")
      (node (ref "R32") (pin "2") (pinfunction "2_2") (pintype "passive"))
      (node (ref "U4") (pin "7") (pinfunction "QH_7") (pintype "output"))
    )
    (net (code "47") (name "LED33") (class "Default")
      (node (ref "R33") (pin "2") (pinfunction "2_2") (pintype "passive"))
      (node (ref "U5") (pin "15") (pinfunction "QA_15") (pintype "output"))
    )
    (net (code "48") (name "LED34") (class "Default")
      (node (ref "R34") (pin "2") (pinfunction "2_2") (pintype "passive"))
      (node (ref "U5") (pin "1") (pinfunction "QB_1") (pintype "output"))
    )
    (net (code "49") (name "LED35") (class "Default")
      (node (ref "R35") (pin "2") (pinfunction "2_2") (pintype "passive"))
      (node (ref "U5") (pin "2") (pinfunction "QC_2") (pintype "output"))
    )
    (net (code "50") (name "LED36") (class "Default")
      (node (ref "R36") (pin "2") (pinfunction "2_2") (pintype "passive"))
      (node (ref "U5") (pin "3") (pinfunction "QD_3") (pintype "output"))
    )
    (net (code "51") (name "LED37") (class "Default")
      (node (ref "R37") (pin "2") (pinfunction "2_2") (pintype "passive"))
      (node (ref "U5") (pin "4") (pinfunction "QE_4") (pintype "output"))
    )
    (net (code "52") (name "LED38") (class "Default")
      (node (ref "R38") (pin "2") (pinfunction "2_2") (pintype "passive"))
      (node (ref "U5") (pin "5") (pinfunction "QF_5") (pintype "output"))
    )
    (net (code "53") (name "LED39") (class "Default")
      (node (ref "R39") (pin "2") (pinfunction "2_2") (pintype "passive"))
      (node (ref "U5") (pin "6") (pinfunction "QG_6") (pintype "output"))
    )
    (net (code "54") (name "LED40") (class "Default")
      (node (ref "R40") (pin "2") (pinfunction "2_2") (pintype "passive"))
      (node (ref "U5") (pin "7") (pinfunction "QH_7") (pintype "output"))
    )
    (net (code "55") (name "LED41") (class "Default")
      (node (ref "R41") (pin "2") (pinfunction "2_2") (pintype "passive"))
      (node (ref "U6") (pin "15") (pinfunction "QA_15") (pintype "output"))
    )
    (net (code "56") (name "LED42") (class "Default")
      (node (ref "R42") (pin "2") (pinfunction "2_2") (pintype "passive"))
      (node (ref "U6") (pin "1") (pinfunction "QB_1") (pintype "output"))
    )
    (net (code "57") (name "LED43") (class "Default")
      (node (ref "R43") (pin "2") (pinfunction "2_2") (pintype "passive"))
      (node (ref "U6") (pin "2") (pinfunction "QC_2") (pintype "output"))
    )
    (net (code "58") (name "LED44") (class "Default")
      (node (ref "R44") (pin "2") (pinfunction "2_2") (pintype "passive"))
      (node (ref "U6") (pin "3") (pinfunction "QD_3") (pintype "output"))
    )
    (net (code "59") (name "LED45") (class "Default")
      (node (ref "R45") (pin "2") (pinfunction "2_2") (pintype "passive"))
      (node (ref "U6") (pin "4") (pinfunction "QE_4") (pintype "output"))
    )
    (net (code "60") (name "LED46") (class "Default")
      (node (ref "R46") (pin "2") (pinfunction "2_2") (pintype "passive"))
      (node (ref "U6") (pin "5") (pinfunction "QF_5") (pintype "output"))
    )
    (net (code "61") (name "LED47") (class "Default")
      (node (ref "R47") (pin "2") (pinfunction "2_2") (pintype "passive"))
      (node (ref "U6") (pin "6") (pinfunction "QG_6") (pintype "output"))
    )
    (net (code "62") (name "LED48") (class "Default")
      (node (ref "R48") (pin "2") (pinfunction "2_2") (pintype "passive"))
      (node (ref "U6") (pin "7") (pinfunction "QH_7") (pintype "output"))
    )
    (net (code "63") (name "LED49") (class "Default")
      (node (ref "R49") (pin "2") (pinfunction "2_2") (pintype "passive"))
      (node (ref "U7") (pin "15") (pinfunction "QA_15") (pintype "output"))
    )
    (net (code "64") (name "LED50") (class "Default")
      (node (ref "R50") (pin "2") (pinfunction "2_2") (pintype "passive"))
      (node (ref "U7") (pin "1") (pinfunction "QB_1") (pintype "output"))
    )
    (net (code "65") (name "LED51") (class "Default")
      (node (ref "R51") (pin "2") (pinfunction "2_2") (pintype "passive"))
      (node (ref "U7") (pin "2") (pinfunction "QC_2") (pintype "output"))
    )
    (net (code "66") (name "LED52") (class "Default")
      (node (ref "R52") (pin "2") (pinfunction "2_2") (pintype "passive"))
      (node (ref "U7") (pin "3") (pinfunction "QD_3") (pintype "output"))
    )
    (net (code "67") (name "LED53") (class "Default")
      (node (ref "R53") (pin "2") (pinfunction "2_2") (pintype "passive"))
      (node (ref "U7") (pin "4") (pinfunction "QE_4") (pintype "output"))
    )
    (net (code "68") (name "LED54") (class "Default")
      (node (ref "R54") (pin "2") (pinfunction "2_2") (pintype "passive"))
      (node (ref "U7") (pin "5") (pinfunction "QF_5") (pintype "output"))
    )
    (net (code "69") (name "LED55") (class "Default")
      (node (ref "R55") (pin "2") (pinfunction "2_2") (pintype "passive"))
      (node (ref "U7") (pin "6") (pinfunction "QG_6") (pintype "output"))
    )
    (net (code "70") (name "LED56") (class "Default")
      (node (ref "R56") (pin "2") (pinfunction "2_2") (pintype "passive"))
      (node (ref "U7") (pin "7") (pinfunction "QH_7") (pintype "output"))
    )
    (net (code "71") (name "LED57") (class "Default")
      (node (ref "R57") (pin "2") (pinfunction "2_2") (pintype "passive"))
      (node (ref "U8") (pin "15") (pinfunction "QA_15") (pintype "output"))
    )
    (net (code "72") (name "LED58") (class "Default")
      (node (ref "R58") (pin "2") (pinfunction "2_2") (pintype "passive"))
      (node (ref "U8") (pin "1") (pinfunction "QB_1") (pintype "output"))
    )
    (net (code "73") (name "LED59") (class "Default")
      (node (ref "R59") (pin "2") (pinfunction "2_2") (pintype "passive"))
      (node (ref "U8") (pin "2") (pinfunction "QC_2") (pintype "output"))
    )
    (net (code "74") (name "LED60") (class "Default")
      (node (ref "R60") (pin "2") (pinfunction "2_2") (pintype "passive"))
      (node (ref "U8") (pin "3") (pinfunction "QD_3") (pintype "output"))
    )
    (net (code "75") (name "LED61") (class "Default")
      (node (ref "R61") (pin "2") (pinfunction "2_2") (pintype "passive"))
      (node (ref "U8") (pin "4") (pinfunction "QE_4") (pintype "output"))
    )
    (net (code "76") (name "LED62") (class "Default")
      (node (ref "R62") (pin "2") (pinfunction "2_2") (pintype "passive"))
      (node (ref "U8") (pin "5") (pinfunction "QF_5") (pintype "output"))
    )
    (net (code "77") (name "LED63") (class "Default")
      (node (ref "R63") (pin "2") (pinfunction "2_2") (pintype "passive"))
      (node (ref "U8") (pin "6") (pinfunction "QG_6") (pintype "output"))
    )
    (net (code "78") (name "LED64") (class "Default")
      (node (ref "R64") (pin "2") (pinfunction "2_2") (pintype "passive"))
      (node (ref "U8") (pin "7") (pinfunction "QH_7") (pintype "output"))
    )
    (net (code "79") (name "MCU_LAYER1") (class "Default")
      (node (ref "R65") (pin "2") (pinfunction "2_2") (pintype "passive"))
      (node (ref "R66") (pin "2") (pinfunction "2_2") (pintype "passive"))
      (node (ref "U9") (pin "D23") (pinfunction "IO23_D23") (pintype "bidirectional"))
    )
    (net (code "80") (name "MCU_LAYER2") (class "Default")
      (node (ref "R68") (pin "2") (pinfunction "2_2") (pintype "passive"))
      (node (ref "R69") (pin "2") (pinfunction "2_2") (pintype "passive"))
      (node (ref "U9") (pin "D22") (pinfunction "IO22_D22") (pintype "bidirectional"))
    )
    (net (code "81") (name "MCU_LAYER3") (class "Default")
      (node (ref "R71") (pin "2") (pinfunction "2_2") (pintype "passive"))
      (node (ref "R72") (pin "2") (pinfunction "2_2") (pintype "passive"))
      (node (ref "U9") (pin "D21") (pinfunction "IO21_D21") (pintype "bidirectional"))
    )
    (net (code "82") (name "MCU_LAYER4") (class "Default")
      (node (ref "R74") (pin "2") (pinfunction "2_2") (pintype "passive"))
      (node (ref "R75") (pin "2") (pinfunction "2_2") (pintype "passive"))
      (node (ref "U9") (pin "D19") (pinfunction "IO19_D19") (pintype "bidirectional"))
    )
    (net (code "83") (name "MCU_LAYER5") (class "Default")
      (node (ref "R77") (pin "2") (pinfunction "2_2") (pintype "passive"))
      (node (ref "R78") (pin "2") (pinfunction "2_2") (pintype "passive"))
      (node (ref "U9") (pin "D18") (pinfunction "IO18_D18") (pintype "bidirectional"))
    )
    (net (code "84") (name "MCU_LAYER6") (class "Default")
      (node (ref "R80") (pin "2") (pinfunction "2_2") (pintype "passive"))
      (node (ref "R81") (pin "2") (pinfunction "2_2") (pintype "passive"))
      (node (ref "U9") (pin "D17") (pinfunction "IO17_D17") (pintype "bidirectional"))
    )
    (net (code "85") (name "MCU_LAYER7") (class "Default")
      (node (ref "R83") (pin "2") (pinfunction "2_2") (pintype "passive"))
      (node (ref "R84") (pin "2") (pinfunction "2_2") (pintype "passive"))
      (node (ref "U9") (pin "D16") (pinfunction "IO16_D16") (pintype "bidirectional"))
    )
    (net (code "86") (name "MCU_LAYER8") (class "Default")
      (node (ref "R86") (pin "2") (pinfunction "2_2") (pintype "passive"))
      (node (ref "R87") (pin "2") (pinfunction "2_2") (pintype "passive"))
      (node (ref "U9") (pin "D4") (pinfunction "IO4_D4") (pintype "bidirectional"))
    )
    (net (code "87") (name "Net-(J2-Pad1)") (class "Default")
      (node (ref "J2") (pin "1") (pinfunction "1_1") (pintype "passive"))
      (node (ref "R91") (pin "1") (pinfunction "1_1") (pintype "passive"))
    )
    (net (code "88") (name "Net-(J3-Pad1)") (class "Default")
      (node (ref "J3") (pin "1") (pinfunction "1_1") (pintype "passive"))
      (node (ref "R92") (pin "1") (pinfunction "1_1") (pintype "passive"))
      (node (ref "R93") (pin "1") (pinfunction "1_1") (pintype "passive"))
    )
    (net (code "89") (name "Net-(J4-Pad1)") (class "Default")
      (node (ref "J4") (pin "1") (pinfunction "1_1") (pintype "passive"))
      (node (ref "R94") (pin "1") (pinfunction "1_1") (pintype "passive"))
      (node (ref "R95") (pin "1") (pinfunction "1_1") (pintype "passive"))
    )
    (net (code "90") (name "Net-(Q1-B)") (class "Default")
      (node (ref "Q1") (pin "2") (pinfunction "B_2") (pintype "passive"))
      (node (ref "R65") (pin "1") (pinfunction "1_1") (pintype "passive"))
    )
    (net (code "91") (name "Net-(Q2-B)") (class "Default")
      (node (ref "Q2") (pin "2") (pinfunction "B_2") (pintype "passive"))
      (node (ref "R66") (pin "1") (pinfunction "1_1") (pintype "passive"))
    )
    (net (code "92") (name "Net-(Q3-B)") (class "Default")
      (node (ref "Q3") (pin "2") (pinfunction "B_2") (pintype "passive"))
      (node (ref "R68") (pin "1") (pinfunction "1_1") (pintype "passive"))
    )
    (net (code "93") (name "Net-(Q4-B)") (class "Default")
      (node (ref "Q4") (pin "2") (pinfunction "B_2") (pintype "passive"))
      (node (ref "R69") (pin "1") (pinfunction "1_1") (pintype "passive"))
    )
    (net (code "94") (name "Net-(Q5-B)") (class "Default")
      (node (ref "Q5") (pin "2") (pinfunction "B_2") (pintype "passive"))
      (node (ref "R71") (pin "1") (pinfunction "1_1") (pintype "passive"))
    )
    (net (code "95") (name "Net-(Q6-B)") (class "Default")
      (node (ref "Q6") (pin "2") (pinfunction "B_2") (pintype "passive"))
      (node (ref "R72") (pin "1") (pinfunction "1_1") (pintype "passive"))
    )
    (net (code "96") (name "Net-(Q7-B)") (class "Default")
      (node (ref "Q7") (pin "2") (pinfunction "B_2") (pintype "passive"))
      (node (ref "R74") (pin "1") (pinfunction "1_1") (pintype "passive"))
    )
    (net (code "97") (name "Net-(Q8-B)") (class "Default")
      (node (ref "Q8") (pin "2") (pinfunction "B_2") (pintype "passive"))
      (node (ref "R75") (pin "1") (pinfunction "1_1") (pintype "passive"))
    )
    (net (code "98") (name "Net-(Q9-B)") (class "Default")
      (node (ref "Q9") (pin "2") (pinfunction "B_2") (pintype "passive"))
      (node (ref "R77") (pin "1") (pinfunction "1_1") (pintype "passive"))
    )
    (net (code "99") (name "Net-(Q10-B)") (class "Default")
      (node (ref "Q10") (pin "2") (pinfunction "B_2") (pintype "passive"))
      (node (ref "R78") (pin "1") (pinfunction "1_1") (pintype "passive"))
    )
    (net (code "100") (name "Net-(Q11-B)") (class "Default")
      (node (ref "Q11") (pin "2") (pinfunction "B_2") (pintype "passive"))
      (node (ref "R80") (pin "1") (pinfunction "1_1") (pintype "passive"))
    )
    (net (code "101") (name "Net-(Q12-B)") (class "Default")
      (node (ref "Q12") (pin "2") (pinfunction "B_2") (pintype "passive"))
      (node (ref "R81") (pin "1") (pinfunction "1_1") (pintype "passive"))
    )
    (net (code "102") (name "Net-(Q13-B)") (class "Default")
      (node (ref "Q13") (pin "2") (pinfunction "B_2") (pintype "passive"))
      (node (ref "R83") (pin "1") (pinfunction "1_1") (pintype "passive"))
    )
    (net (code "103") (name "Net-(Q14-B)") (class "Default")
      (node (ref "Q14") (pin "2") (pinfunction "B_2") (pintype "passive"))
      (node (ref "R84") (pin "1") (pinfunction "1_1") (pintype "passive"))
    )
    (net (code "104") (name "Net-(Q15-B)") (class "Default")
      (node (ref "Q15") (pin "2") (pinfunction "B_2") (pintype "passive"))
      (node (ref "R86") (pin "1") (pinfunction "1_1") (pintype "passive"))
    )
    (net (code "105") (name "Net-(Q16-B)") (class "Default")
      (node (ref "Q16") (pin "2") (pinfunction "B_2") (pintype "passive"))
      (node (ref "R87") (pin "1") (pinfunction "1_1") (pintype "passive"))
    )
    (net (code "106") (name "Net-(R1-Pad1)") (class "Default")
      (node (ref "R1") (pin "1") (pinfunction "1_1") (pintype "passive"))
      (node (ref "X1") (pin "1") (pinfunction "1_1") (pintype "passive"))
    )
    (net (code "107") (name "Net-(R2-Pad1)") (class "Default")
      (node (ref "R2") (pin "1") (pinfunction "1_1") (pintype "passive"))
      (node (ref "X1") (pin "2") (pinfunction "2_2") (pintype "passive"))
    )
    (net (code "108") (name "Net-(R3-Pad1)") (class "Default")
      (node (ref "R3") (pin "1") (pinfunction "1_1") (pintype "passive"))
      (node (ref "X1") (pin "3") (pinfunction "3_3") (pintype "passive"))
    )
    (net (code "109") (name "Net-(R4-Pad1)") (class "Default")
      (node (ref "R4") (pin "1") (pinfunction "1_1") (pintype "passive"))
      (node (ref "X1") (pin "4") (pinfunction "4_4") (pintype "passive"))
    )
    (net (code "110") (name "Net-(R5-Pad1)") (class "Default")
      (node (ref "R5") (pin "1") (pinfunction "1_1") (pintype "passive"))
      (node (ref "X1") (pin "5") (pinfunction "5_5") (pintype "passive"))
    )
    (net (code "111") (name "Net-(R6-Pad1)") (class "Default")
      (node (ref "R6") (pin "1") (pinfunction "1_1") (pintype "passive"))
      (node (ref "X1") (pin "6") (pinfunction "6_6") (pintype "passive"))
    )
    (net (code "112") (name "Net-(R7-Pad1)") (class "Default")
      (node (ref "R7") (pin "1") (pinfunction "1_1") (pintype "passive"))
      (node (ref "X1") (pin "7") (pinfunction "7_7") (pintype "passive"))
    )
    (net (code "113") (name "Net-(R8-Pad1)") (class "Default")
      (node (ref "R8") (pin "1") (pinfunction "1_1") (pintype "passive"))
      (node (ref "X1") (pin "8") (pinfunction "8_8") (pintype "passive"))
    )
    (net (code "114") (name "Net-(R9-Pad1)") (class "Default")
      (node (ref "R9") (pin "1") (pinfunction "1_1") (pintype "passive"))
      (node (ref "X2") (pin "1") (pinfunction "1_1") (pintype "passive"))
    )
    (net (code "115") (name "Net-(R10-Pad1)") (class "Default")
      (node (ref "R10") (pin "1") (pinfunction "1_1") (pintype "passive"))
      (node (ref "X2") (pin "2") (pinfunction "2_2") (pintype "passive"))
    )
    (net (code "116") (name "Net-(R11-Pad1)") (class "Default")
      (node (ref "R11") (pin "1") (pinfunction "1_1") (pintype "passive"))
      (node (ref "X2") (pin "3") (pinfunction "3_3") (pintype "passive"))
    )
    (net (code "117") (name "Net-(R12-Pad1)") (class "Default")
      (node (ref "R12") (pin "1") (pinfunction "1_1") (pintype "passive"))
      (node (ref "X2") (pin "4") (pinfunction "4_4") (pintype "passive"))
    )
    (net (code "118") (name "Net-(R13-Pad1)") (class "Default")
      (node (ref "R13") (pin "1") (pinfunction "1_1") (pintype "passive"))
      (node (ref "X2") (pin "5") (pinfunction "5_5") (pintype "passive"))
    )
    (net (code "119") (name "Net-(R14-Pad1)") (class "Default")
      (node (ref "R14") (pin "1") (pinfunction "1_1") (pintype "passive"))
      (node (ref "X2") (pin "6") (pinfunction "6_6") (pintype "passive"))
    )
    (net (code "120") (name "Net-(R15-Pad1)") (class "Default")
      (node (ref "R15") (pin "1") (pinfunction "1_1") (pintype "passive"))
      (node (ref "X2") (pin "7") (pinfunction "7_7") (pintype "passive"))
    )
    (net (code "121") (name "Net-(R16-Pad1)") (class "Default")
      (node (ref "R16") (pin "1") (pinfunction "1_1") (pintype "passive"))
      (node (ref "X2") (pin "8") (pinfunction "8_8") (pintype "passive"))
    )
    (net (code "122") (name "Net-(R17-Pad1)") (class "Default")
      (node (ref "R17") (pin "1") (pinfunction "1_1") (pintype "passive"))
      (node (ref "X3") (pin "1") (pinfunction "1_1") (pintype "passive"))
    )
    (net (code "123") (name "Net-(R18-Pad1)") (class "Default")
      (node (ref "R18") (pin "1") (pinfunction "1_1") (pintype "passive"))
      (node (ref "X3") (pin "2") (pinfunction "2_2") (pintype "passive"))
    )
    (net (code "124") (name "Net-(R19-Pad1)") (class "Default")
      (node (ref "R19") (pin "1") (pinfunction "1_1") (pintype "passive"))
      (node (ref "X3") (pin "3") (pinfunction "3_3") (pintype "passive"))
    )
    (net (code "125") (name "Net-(R20-Pad1)") (class "Default")
      (node (ref "R20") (pin "1") (pinfunction "1_1") (pintype "passive"))
      (node (ref "X3") (pin "4") (pinfunction "4_4") (pintype "passive"))
    )
    (net (code "126") (name "Net-(R21-Pad1)") (class "Default")
      (node (ref "R21") (pin "1") (pinfunction "1_1") (pintype "passive"))
      (node (ref "X3") (pin "5") (pinfunction "5_5") (pintype "passive"))
    )
    (net (code "127") (name "Net-(R22-Pad1)") (class "Default")
      (node (ref "R22") (pin "1") (pinfunction "1_1") (pintype "passive"))
      (node (ref "X3") (pin "6") (pinfunction "6_6") (pintype "passive"))
    )
    (net (code "128") (name "Net-(R23-Pad1)") (class "Default")
      (node (ref "R23") (pin "1") (pinfunction "1_1") (pintype "passive"))
      (node (ref "X3") (pin "7") (pinfunction "7_7") (pintype "passive"))
    )
    (net (code "129") (name "Net-(R24-Pad1)") (class "Default")
      (node (ref "R24") (pin "1") (pinfunction "1_1") (pintype "passive"))
      (node (ref "X3") (pin "8") (pinfunction "8_8") (pintype "passive"))
    )
    (net (code "130") (name "Net-(R25-Pad1)") (class "Default")
      (node (ref "R25") (pin "1") (pinfunction "1_1") (pintype "passive"))
      (node (ref "X4") (pin "1") (pinfunction "1_1") (pintype "passive"))
    )
    (net (code "131") (name "Net-(R26-Pad1)") (class "Default")
      (node (ref "R26") (pin "1") (pinfunction "1_1") (pintype "passive"))
      (node (ref "X4") (pin "2") (pinfunction "2_2") (pintype "passive"))
    )
    (net (code "132") (name "Net-(R27-Pad1)") (class "Default")
      (node (ref "R27") (pin "1") (pinfunction "1_1") (pintype "passive"))
      (node (ref "X4") (pin "3") (pinfunction "3_3") (pintype "passive"))
    )
    (net (code "133") (name "Net-(R28-Pad1)") (class "Default")
      (node (ref "R28") (pin "1") (pinfunction "1_1") (pintype "passive"))
      (node (ref "X4") (pin "4") (pinfunction "4_4") (pintype "passive"))
    )
    (net (code "134") (name "Net-(R29-Pad1)") (class "Default")
      (node (ref "R29") (pin "1") (pinfunction "1_1") (pintype "passive"))
      (node (ref "X4") (pin "5") (pinfunction "5_5") (pintype "passive"))
    )
    (net (code "135") (name "Net-(R30-Pad1)") (class "Default")
      (node (ref "R30") (pin "1") (pinfunction "1_1") (pintype "passive"))
      (node (ref "X4") (pin "6") (pinfunction "6_6") (pintype "passive"))
    )
    (net (code "136") (name "Net-(R31-Pad1)") (class "Default")
      (node (ref "R31") (pin "1") (pinfunction "1_1") (pintype "passive"))
      (node (ref "X4") (pin "7") (pinfunction "7_7") (pintype "passive"))
    )
    (net (code "137") (name "Net-(R32-Pad1)") (class "Default")
      (node (ref "R32") (pin "1") (pinfunction "1_1") (pintype "passive"))
      (node (ref "X4") (pin "8") (pinfunction "8_8") (pintype "passive"))
    )
    (net (code "138") (name "Net-(R33-Pad1)") (class "Default")
      (node (ref "R33") (pin "1") (pinfunction "1_1") (pintype "passive"))
      (node (ref "X5") (pin "1") (pinfunction "1_1") (pintype "passive"))
    )
    (net (code "139") (name "Net-(R34-Pad1)") (class "Default")
      (node (ref "R34") (pin "1") (pinfunction "1_1") (pintype "passive"))
      (node (ref "X5") (pin "2") (pinfunction "2_2") (pintype "passive"))
    )
    (net (code "140") (name "Net-(R35-Pad1)") (class "Default")
      (node (ref "R35") (pin "1") (pinfunction "1_1") (pintype "passive"))
      (node (ref "X5") (pin "3") (pinfunction "3_3") (pintype "passive"))
    )
    (net (code "141") (name "Net-(R36-Pad1)") (class "Default")
      (node (ref "R36") (pin "1") (pinfunction "1_1") (pintype "passive"))
      (node (ref "X5") (pin "4") (pinfunction "4_4") (pintype "passive"))
    )
    (net (code "142") (name "Net-(R37-Pad1)") (class "Default")
      (node (ref "R37") (pin "1") (pinfunction "1_1") (pintype "passive"))
      (node (ref "X5") (pin "5") (pinfunction "5_5") (pintype "passive"))
    )
    (net (code "143") (name "Net-(R38-Pad1)") (class "Default")
      (node (ref "R38") (pin "1") (pinfunction "1_1") (pintype "passive"))
      (node (ref "X5") (pin "6") (pinfunction "6_6") (pintype "passive"))
    )
    (net (code "144") (name "Net-(R39-Pad1)") (class "Default")
      (node (ref "R39") (pin "1") (pinfunction "1_1") (pintype "passive"))
      (node (ref "X5") (pin "7") (pinfunction "7_7") (pintype "passive"))
    )
    (net (code "145") (name "Net-(R40-Pad1)") (class "Default")
      (node (ref "R40") (pin "1") (pinfunction "1_1") (pintype "passive"))
      (node (ref "X5") (pin "8") (pinfunction "8_8") (pintype "passive"))
    )
    (net (code "146") (name "Net-(R41-Pad1)") (class "Default")
      (node (ref "R41") (pin "1") (pinfunction "1_1") (pintype "passive"))
      (node (ref "X6") (pin "1") (pinfunction "1_1") (pintype "passive"))
    )
    (net (code "147") (name "Net-(R42-Pad1)") (class "Default")
      (node (ref "R42") (pin "1") (pinfunction "1_1") (pintype "passive"))
      (node (ref "X6") (pin "2") (pinfunction "2_2") (pintype "passive"))
    )
    (net (code "148") (name "Net-(R43-Pad1)") (class "Default")
      (node (ref "R43") (pin "1") (pinfunction "1_1") (pintype "passive"))
      (node (ref "X6") (pin "3") (pinfunction "3_3") (pintype "passive"))
    )
    (net (code "149") (name "Net-(R44-Pad1)") (class "Default")
      (node (ref "R44") (pin "1") (pinfunction "1_1") (pintype "passive"))
      (node (ref "X6") (pin "4") (pinfunction "4_4") (pintype "passive"))
    )
    (net (code "150") (name "Net-(R45-Pad1)") (class "Default")
      (node (ref "R45") (pin "1") (pinfunction "1_1") (pintype "passive"))
      (node (ref "X6") (pin "5") (pinfunction "5_5") (pintype "passive"))
    )
    (net (code "151") (name "Net-(R46-Pad1)") (class "Default")
      (node (ref "R46") (pin "1") (pinfunction "1_1") (pintype "passive"))
      (node (ref "X6") (pin "6") (pinfunction "6_6") (pintype "passive"))
    )
    (net (code "152") (name "Net-(R47-Pad1)") (class "Default")
      (node (ref "R47") (pin "1") (pinfunction "1_1") (pintype "passive"))
      (node (ref "X6") (pin "7") (pinfunction "7_7") (pintype "passive"))
    )
    (net (code "153") (name "Net-(R48-Pad1)") (class "Default")
      (node (ref "R48") (pin "1") (pinfunction "1_1") (pintype "passive"))
      (node (ref "X6") (pin "8") (pinfunction "8_8") (pintype "passive"))
    )
    (net (code "154") (name "Net-(R49-Pad1)") (class "Default")
      (node (ref "R49") (pin "1") (pinfunction "1_1") (pintype "passive"))
      (node (ref "X7") (pin "1") (pinfunction "1_1") (pintype "passive"))
    )
    (net (code "155") (name "Net-(R50-Pad1)") (class "Default")
      (node (ref "R50") (pin "1") (pinfunction "1_1") (pintype "passive"))
      (node (ref "X7") (pin "2") (pinfunction "2_2") (pintype "passive"))
    )
    (net (code "156") (name "Net-(R51-Pad1)") (class "Default")
      (node (ref "R51") (pin "1") (pinfunction "1_1") (pintype "passive"))
      (node (ref "X7") (pin "3") (pinfunction "3_3") (pintype "passive"))
    )
    (net (code "157") (name "Net-(R52-Pad1)") (class "Default")
      (node (ref "R52") (pin "1") (pinfunction "1_1") (pintype "passive"))
      (node (ref "X7") (pin "4") (pinfunction "4_4") (pintype "passive"))
    )
    (net (code "158") (name "Net-(R53-Pad1)") (class "Default")
      (node (ref "R53") (pin "1") (pinfunction "1_1") (pintype "passive"))
      (node (ref "X7") (pin "5") (pinfunction "5_5") (pintype "passive"))
    )
    (net (code "159") (name "Net-(R54-Pad1)") (class "Default")
      (node (ref "R54") (pin "1") (pinfunction "1_1") (pintype "passive"))
      (node (ref "X7") (pin "6") (pinfunction "6_6") (pintype "passive"))
    )
    (net (code "160") (name "Net-(R55-Pad1)") (class "Default")
      (node (ref "R55") (pin "1") (pinfunction "1_1") (pintype "passive"))
      (node (ref "X7") (pin "7") (pinfunction "7_7") (pintype "passive"))
    )
    (net (code "161") (name "Net-(R56-Pad1)") (class "Default")
      (node (ref "R56") (pin "1") (pinfunction "1_1") (pintype "passive"))
      (node (ref "X7") (pin "8") (pinfunction "8_8") (pintype "passive"))
    )
    (net (code "162") (name "Net-(R57-Pad1)") (class "Default")
      (node (ref "R57") (pin "1") (pinfunction "1_1") (pintype "passive"))
      (node (ref "X8") (pin "1") (pinfunction "1_1") (pintype "passive"))
    )
    (net (code "163") (name "Net-(R58-Pad1)") (class "Default")
      (node (ref "R58") (pin "1") (pinfunction "1_1") (pintype "passive"))
      (node (ref "X8") (pin "2") (pinfunction "2_2") (pintype "passive"))
    )
    (net (code "164") (name "Net-(R59-Pad1)") (class "Default")
      (node (ref "R59") (pin "1") (pinfunction "1_1") (pintype "passive"))
      (node (ref "X8") (pin "3") (pinfunction "3_3") (pintype "passive"))
    )
    (net (code "165") (name "Net-(R60-Pad1)") (class "Default")
      (node (ref "R60") (pin "1") (pinfunction "1_1") (pintype "passive"))
      (node (ref "X8") (pin "4") (pinfunction "4_4") (pintype "passive"))
    )
    (net (code "166") (name "Net-(R61-Pad1)") (class "Default")
      (node (ref "R61") (pin "1") (pinfunction "1_1") (pintype "passive"))
      (node (ref "X8") (pin "5") (pinfunction "5_5") (pintype "passive"))
    )
    (net (code "167") (name "Net-(R62-Pad1)") (class "Default")
      (node (ref "R62") (pin "1") (pinfunction "1_1") (pintype "passive"))
      (node (ref "X8") (pin "6") (pinfunction "6_6") (pintype "passive"))
    )
    (net (code "168") (name "Net-(R63-Pad1)") (class "Default")
      (node (ref "R63") (pin "1") (pinfunction "1_1") (pintype "passive"))
      (node (ref "X8") (pin "7") (pinfunction "7_7") (pintype "passive"))
    )
    (net (code "169") (name "Net-(R64-Pad1)") (class "Default")
      (node (ref "R64") (pin "1") (pinfunction "1_1") (pintype "passive"))
      (node (ref "X8") (pin "8") (pinfunction "8_8") (pintype "passive"))
    )
    (net (code "170") (name "Net-(U10-CB)") (class "Default")
      (node (ref "C14") (pin "2") (pinfunction "2_2") (pintype "passive"))
      (node (ref "U10") (pin "3") (pinfunction "CB_3") (pintype "input"))
    )
    (net (code "171") (name "SR_CLOCK") (class "Default")
      (node (ref "U1") (pin "11") (pinfunction "SRCLK_11") (pintype "input"))
      (node (ref "U2") (pin "11") (pinfunction "SRCLK_11") (pintype "input"))
      (node (ref "U3") (pin "11") (pinfunction "SRCLK_11") (pintype "input"))
      (node (ref "U4") (pin "11") (pinfunction "SRCLK_11") (pintype "input"))
      (node (ref "U5") (pin "11") (pinfunction "SRCLK_11") (pintype "input"))
      (node (ref "U6") (pin "11") (pinfunction "SRCLK_11") (pintype "input"))
      (node (ref "U7") (pin "11") (pinfunction "SRCLK_11") (pintype "input"))
      (node (ref "U8") (pin "11") (pinfunction "SRCLK_11") (pintype "input"))
      (node (ref "U9") (pin "D33") (pinfunction "IO33_D33") (pintype "bidirectional"))
    )
    (net (code "172") (name "SR_DATA_1-8") (class "Default")
      (node (ref "U1") (pin "14") (pinfunction "SER_14") (pintype "input"))
      (node (ref "U9") (pin "D27") (pinfunction "IO27_D27") (pintype "bidirectional"))
    )
    (net (code "173") (name "SR_DATA_9-16") (class "Default")
      (node (ref "U1") (pin "9") (pinfunction "QH_2_9") (pintype "output"))
      (node (ref "U2") (pin "14") (pinfunction "SER_14") (pintype "input"))
    )
    (net (code "174") (name "SR_DATA_17-24") (class "Default")
      (node (ref "U2") (pin "9") (pinfunction "QH_2_9") (pintype "output"))
      (node (ref "U3") (pin "14") (pinfunction "SER_14") (pintype "input"))
    )
    (net (code "175") (name "SR_DATA_25-32") (class "Default")
      (node (ref "U3") (pin "9") (pinfunction "QH_2_9") (pintype "output"))
      (node (ref "U4") (pin "14") (pinfunction "SER_14") (pintype "input"))
    )
    (net (code "176") (name "SR_DATA_33-40") (class "Default")
      (node (ref "U4") (pin "9") (pinfunction "QH_2_9") (pintype "output"))
      (node (ref "U5") (pin "14") (pinfunction "SER_14") (pintype "input"))
    )
    (net (code "177") (name "SR_DATA_41-48") (class "Default")
      (node (ref "U5") (pin "9") (pinfunction "QH_2_9") (pintype "output"))
      (node (ref "U6") (pin "14") (pinfunction "SER_14") (pintype "input"))
    )
    (net (code "178") (name "SR_DATA_49-56") (class "Default")
      (node (ref "U6") (pin "9") (pinfunction "QH_2_9") (pintype "output"))
      (node (ref "U7") (pin "14") (pinfunction "SER_14") (pintype "input"))
    )
    (net (code "179") (name "SR_DATA_57-64") (class "Default")
      (node (ref "U7") (pin "9") (pinfunction "QH_2_9") (pintype "output"))
      (node (ref "U8") (pin "14") (pinfunction "SER_14") (pintype "input"))
    )
    (net (code "180") (name "SR_ENABLE") (class "Default")
      (node (ref "U1") (pin "13") (pinfunction "~{OE}_13") (pintype "input"))
      (node (ref "U2") (pin "13") (pinfunction "~{OE}_13") (pintype "input"))
      (node (ref "U3") (pin "13") (pinfunction "~{OE}_13") (pintype "input"))
      (node (ref "U4") (pin "13") (pinfunction "~{OE}_13") (pintype "input"))
      (node (ref "U5") (pin "13") (pinfunction "~{OE}_13") (pintype "input"))
      (node (ref "U6") (pin "13") (pinfunction "~{OE}_13") (pintype "input"))
      (node (ref "U7") (pin "13") (pinfunction "~{OE}_13") (pintype "input"))
      (node (ref "U8") (pin "13") (pinfunction "~{OE}_13") (pintype "input"))
      (node (ref "U9") (pin "D26") (pinfunction "IO26_D26") (pintype "bidirectional"))
    )
    (net (code "181") (name "SR_LATCH") (class "Default")
      (node (ref "U1") (pin "12") (pinfunction "RCLK_12") (pintype "input"))
      (node (ref "U2") (pin "12") (pinfunction "RCLK_12") (pintype "input"))
      (node (ref "U3") (pin "12") (pinfunction "RCLK_12") (pintype "input"))
      (node (ref "U4") (pin "12") (pinfunction "RCLK_12") (pintype "input"))
      (node (ref "U5") (pin "12") (pinfunction "RCLK_12") (pintype "input"))
      (node (ref "U6") (pin "12") (pinfunction "RCLK_12") (pintype "input"))
      (node (ref "U7") (pin "12") (pinfunction "RCLK_12") (pintype "input"))
      (node (ref "U8") (pin "12") (pinfunction "RCLK_12") (pintype "input"))
      (node (ref "U9") (pin "D25") (pinfunction "IO25_D25") (pintype "bidirectional"))
    )
    (net (code "182") (name "STATUS_LED") (class "Default")
      (node (ref "R91") (pin "2") (pinfunction "2_2") (pintype "passive"))
      (node (ref "U9") (pin "D32") (pinfunction "IO32_D32") (pintype "bidirectional"))
    )
    (net (code "183") (name "TOGGLE_BTN1") (class "Default")
      (node (ref "C16") (pin "1") (pinfunction "1_1") (pintype "passive"))
      (node (ref "R95") (pin "2") (pinfunction "2_2") (pintype "passive"))
      (node (ref "U9") (pin "D34") (pinfunction "IO34_D34") (pintype "bidirectional"))
    )
    (net (code "184") (name "TOGGLE_BTN2") (class "Default")
      (node (ref "C15") (pin "1") (pinfunction "1_1") (pintype "passive"))
      (node (ref "R92") (pin "2") (pinfunction "2_2") (pintype "passive"))
      (node (ref "U9") (pin "D35") (pinfunction "IO35_D35") (pintype "bidirectional"))
    )
    (net (code "185") (name "unconnected-(U8-QH_2-Pad9)") (class "Default")
      (node (ref "U8") (pin "9") (pinfunction "QH_2_9") (pintype "output"))
    )
    (net (code "186") (name "unconnected-(U9-IO1-PadD1)") (class "Default")
      (node (ref "U9") (pin "D1") (pinfunction "IO1_D1") (pintype "bidirectional"))
    )
    (net (code "187") (name "unconnected-(U9-IO2-PadD2)") (class "Default")
      (node (ref "U9") (pin "D2") (pinfunction "IO2_D2") (pintype "bidirectional"))
    )
    (net (code "188") (name "unconnected-(U9-IO3-PadD3)") (class "Default")
      (node (ref "U9") (pin "D3") (pinfunction "IO3_D3") (pintype "bidirectional"))
    )
    (net (code "189") (name "unconnected-(U9-IO5-PadD5)") (class "Default")
      (node (ref "U9") (pin "D5") (pinfunction "IO5_D5") (pintype "bidirectional"))
    )
    (net (code "190") (name "unconnected-(U9-IO12-PadD12)") (class "Default")
      (node (ref "U9") (pin "D12") (pinfunction "IO12_D12") (pintype "bidirectional"))
    )
    (net (code "191") (name "unconnected-(U9-IO13-PadD13)") (class "Default")
      (node (ref "U9") (pin "D13") (pinfunction "IO13_D13") (pintype "bidirectional"))
    )
    (net (code "192") (name "unconnected-(U9-IO14-PadD14)") (class "Default")
      (node (ref "U9") (pin "D14") (pinfunction "IO14_D14") (pintype "bidirectional"))
    )
    (net (code "193") (name "unconnected-(U9-IO15-PadD15)") (class "Default")
      (node (ref "U9") (pin "D15") (pinfunction "IO15_D15") (pintype "bidirectional"))
    )
    (net (code "194") (name "unconnected-(U9-PadEN)") (class "Default")
      (node (ref "U9") (pin "EN") (pinfunction "EN_EN") (pintype "bidirectional"))
    )
    (net (code "195") (name "unconnected-(U9-VN-IO39-PadD39)") (class "Default")
      (node (ref "U9") (pin "D39") (pinfunction "VN-IO39_D39") (pintype "bidirectional"))
    )
    (net (code "196") (name "unconnected-(U9-VP-OI36-PadD36)") (class "Default")
      (node (ref "U9") (pin "D36") (pinfunction "VP-OI36_D36") (pintype "bidirectional"))
    )
    (net (code "197") (name "unconnected-(U10-ON{slash}~{OFF}-Pad7)") (class "Default")
      (node (ref "U10") (pin "7") (pinfunction "ON/~{OFF}_7") (pintype "input"))
    )
  )
)
